# Sheet1.net
KiCad netlist of a schematic drawn in Altium Designer
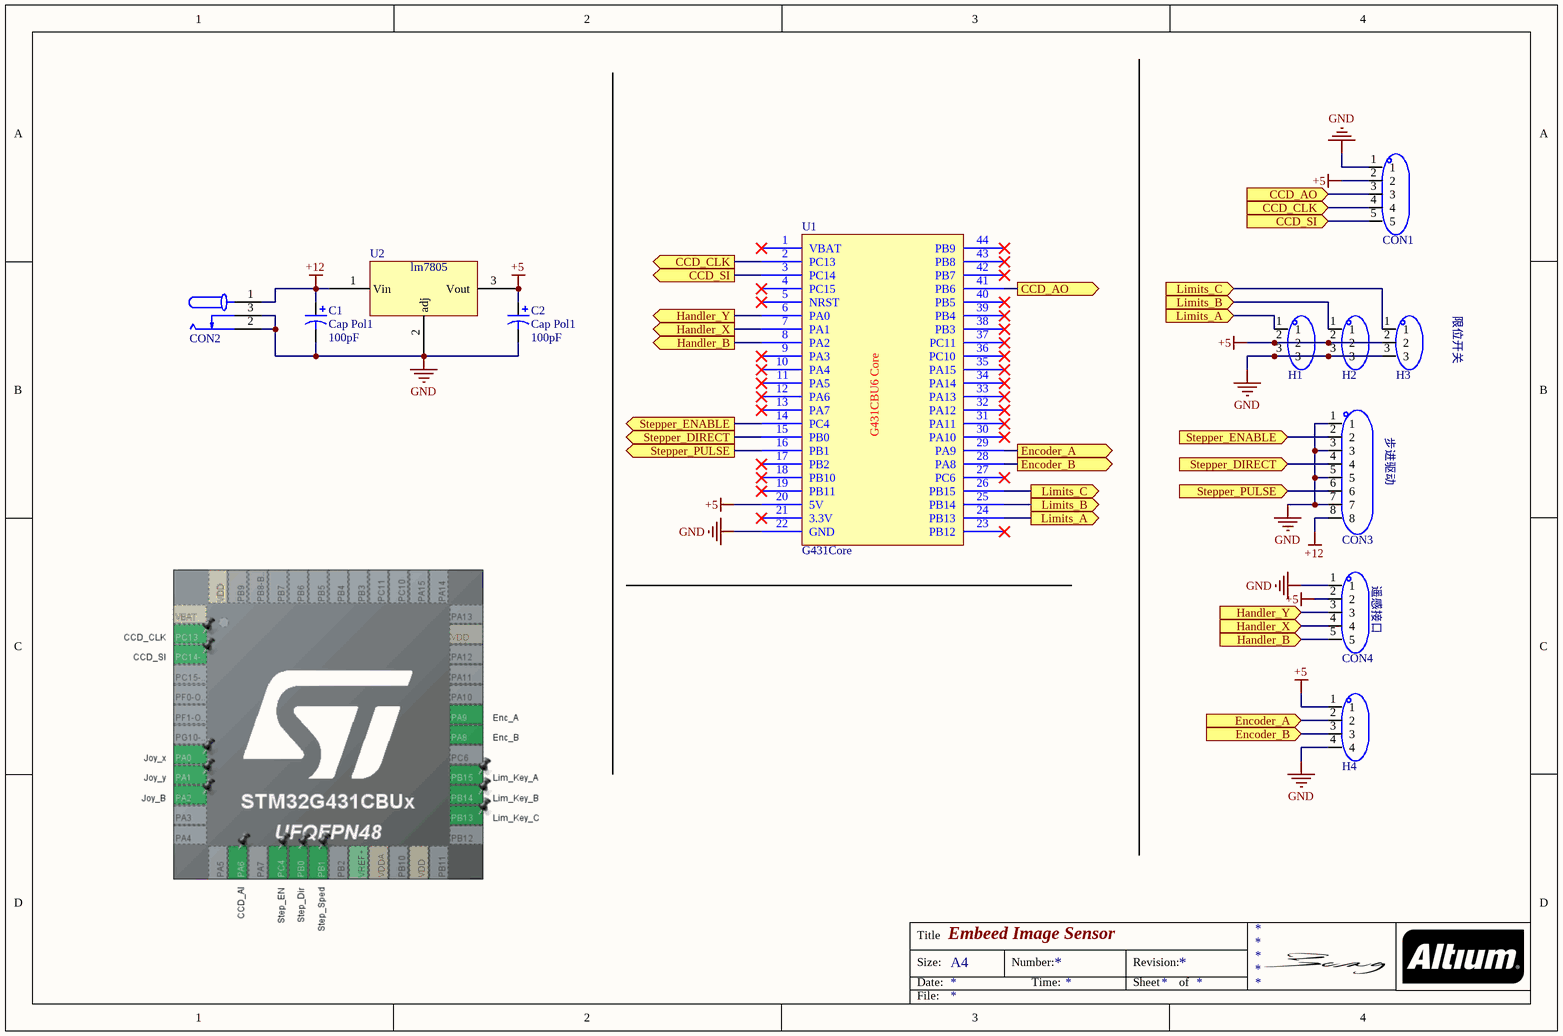
[diagram p0: Sheet1.SchDoc]

(export (version "E")
  (design (tool "Eeschema 10.0.6"))
  (components
    (comp (ref "C1")
      (value "Cap Pol1")
      (footprint "RB7.6-15")
      (description "Polarized Capacitor (Radial)")
      (fields (field (name "ALTIUM_VALUE") "100pF") (field (name "PUBLISHER") "Altium Limited"))
      (libsource (lib "Miscellaneous Devices") (part "Cap Pol1"))
    )
    (comp (ref "C2")
      (value "Cap Pol1")
      (footprint "RB7.6-15")
      (description "Polarized Capacitor (Radial)")
      (fields (field (name "ALTIUM_VALUE") "100pF") (field (name "PUBLISHER") "Altium Limited"))
      (libsource (lib "Miscellaneous Devices") (part "Cap Pol1"))
    )
    (comp (ref "CON1")
      (value "XH2.54-5P")
      (footprint "CONN-TH_5P-P2.50_ZX-XH2.54-5PZZ")
      (fields
        (field (name "MANUFACTURER") "Megastar(兆星)")
        (field (name "MANUFACTURER PART") "ZX-XH2.54-5PZZ")
      )
      (libsource (lib "altium-import") (part "root_0_XH2.54-5P_"))
    )
    (comp (ref "CON2")
      (value "DC_Power_Connector")
      (footprint "DC-IN-TH_DC-005-5A-2.0")
      (fields
        (field (name "MANUFACTURER") "XKB Connection(中国星坤)")
        (field (name "MANUFACTURER PART") "DC-005-5A-2.0")
      )
      (libsource (lib "altium-import") (part "root_0_DC_Power_Connector_"))
    )
    (comp (ref "CON3")
      (value "8Pin_Screw")
      (footprint "CONN-TH_8P-P3.81_WJ15EDGRC-3.81-8P")
      (fields
        (field (name "MANUFACTURER") "KANGNEX(康奈克斯电气)")
        (field (name "MANUFACTURER PART") "WJ15EDGRC-3.81-8P")
      )
      (libsource (lib "altium-import") (part "root_0_8Pin_Screw_"))
    )
    (comp (ref "CON4")
      (value "PH2.0_5Pin")
      (footprint "CONN-TH_5P-P2.00-PH5A")
      (fields (field (name "MANUFACTURER") "XUNPU(讯普)") (field (name "MANUFACTURER PART") "WAFER-PH2.0-5PZZ"))
      (libsource (lib "altium-import") (part "root_0_PH2.0_5Pin_"))
    )
    (comp (ref "H1")
      (value "3Pin_Connector")
      (footprint "HDR-TH_3P-P2.54-V-M")
      (fields (field (name "MANUFACTURER") "XFCN(兴飞)") (field (name "MANUFACTURER PART") "PZ254V-11-03P"))
      (libsource (lib "altium-import") (part "root_0_3Pin_Connector_"))
    )
    (comp (ref "H2")
      (value "3Pin_Connector")
      (footprint "HDR-TH_3P-P2.54-V-M")
      (fields (field (name "MANUFACTURER") "XFCN(兴飞)") (field (name "MANUFACTURER PART") "PZ254V-11-03P"))
      (libsource (lib "altium-import") (part "root_0_3Pin_Connector_"))
    )
    (comp (ref "H3")
      (value "3Pin_Connector")
      (footprint "HDR-TH_3P-P2.54-V-M")
      (fields (field (name "MANUFACTURER") "XFCN(兴飞)") (field (name "MANUFACTURER PART") "PZ254V-11-03P"))
      (libsource (lib "altium-import") (part "root_0_3Pin_Connector_"))
    )
    (comp (ref "H4")
      (value "2.54_4Pin")
      (footprint "HDR-TH_4P-P2.54-V-M")
      (fields (field (name "MANUFACTURER") "XFCN(兴飞)") (field (name "MANUFACTURER PART") "PZ254V-11-04P"))
      (libsource (lib "altium-import") (part "root_0_2.54_4Pin_"))
    )
    (comp (ref "U1")
      (value "G431Core")
      (footprint "PCBComponent_1")
      (libsource (lib "altium-import") (part "root_0_G431Core_"))
    )
    (comp (ref "U2")
      (value "lm7805")
      (footprint "TO-220-3_L10.0-W4.5-P2.54-L")
      (libsource (lib "altium-import") (part "root_0_lm7805_"))
    )
  )
  (nets
    (net (code "1") (name "+5") (class "Default")
      (node (ref "C2") (pin "1") (pinfunction "1_1") (pintype "passive"))
      (node (ref "CON1") (pin "2") (pinfunction "2_2") (pintype "passive"))
      (node (ref "CON4") (pin "2") (pinfunction "2_2") (pintype "passive"))
      (node (ref "H1") (pin "2") (pinfunction "2_2") (pintype "passive"))
      (node (ref "H2") (pin "2") (pinfunction "2_2") (pintype "passive"))
      (node (ref "H3") (pin "2") (pinfunction "2_2") (pintype "passive"))
      (node (ref "H4") (pin "1") (pinfunction "1_1") (pintype "passive"))
      (node (ref "U1") (pin "20") (pinfunction "5V_20") (pintype "passive"))
      (node (ref "U2") (pin "3") (pinfunction "Vout_3") (pintype "passive"))
    )
    (net (code "2") (name "+12") (class "Default")
      (node (ref "C1") (pin "1") (pinfunction "1_1") (pintype "passive"))
      (node (ref "CON2") (pin "1") (pinfunction "1_1") (pintype "passive"))
      (node (ref "CON3") (pin "8") (pinfunction "8_8") (pintype "passive"))
      (node (ref "U2") (pin "1") (pinfunction "Vin_1") (pintype "passive"))
    )
    (net (code "3") (name "/CCD_AO") (class "Default")
      (node (ref "CON1") (pin "3") (pinfunction "3_3") (pintype "passive"))
      (node (ref "U1") (pin "41") (pinfunction "PB6_41") (pintype "passive"))
    )
    (net (code "4") (name "/CCD_CLK") (class "Default")
      (node (ref "CON1") (pin "4") (pinfunction "4_4") (pintype "passive"))
      (node (ref "U1") (pin "2") (pinfunction "PC13_2") (pintype "passive"))
    )
    (net (code "5") (name "/CCD_SI") (class "Default")
      (node (ref "CON1") (pin "5") (pinfunction "5_5") (pintype "passive"))
      (node (ref "U1") (pin "3") (pinfunction "PC14_3") (pintype "passive"))
    )
    (net (code "6") (name "/Encoder_A") (class "Default")
      (node (ref "H4") (pin "2") (pinfunction "2_2") (pintype "passive"))
      (node (ref "U1") (pin "29") (pinfunction "PA9_29") (pintype "passive"))
    )
    (net (code "7") (name "/Encoder_B") (class "Default")
      (node (ref "H4") (pin "3") (pinfunction "3_3") (pintype "passive"))
      (node (ref "U1") (pin "28") (pinfunction "PA8_28") (pintype "passive"))
    )
    (net (code "8") (name "/Handler_B") (class "Default")
      (node (ref "CON4") (pin "5") (pinfunction "5_5") (pintype "passive"))
      (node (ref "U1") (pin "8") (pinfunction "PA2_8") (pintype "passive"))
    )
    (net (code "9") (name "/Handler_X") (class "Default")
      (node (ref "CON4") (pin "4") (pinfunction "4_4") (pintype "passive"))
      (node (ref "U1") (pin "7") (pinfunction "PA1_7") (pintype "passive"))
    )
    (net (code "10") (name "/Handler_Y") (class "Default")
      (node (ref "CON4") (pin "3") (pinfunction "3_3") (pintype "passive"))
      (node (ref "U1") (pin "6") (pinfunction "PA0_6") (pintype "passive"))
    )
    (net (code "11") (name "/Limits_A") (class "Default")
      (node (ref "H1") (pin "1") (pinfunction "1_1") (pintype "passive"))
      (node (ref "U1") (pin "24") (pinfunction "PB13_24") (pintype "passive"))
    )
    (net (code "12") (name "/Limits_B") (class "Default")
      (node (ref "H2") (pin "1") (pinfunction "1_1") (pintype "passive"))
      (node (ref "U1") (pin "25") (pinfunction "PB14_25") (pintype "passive"))
    )
    (net (code "13") (name "/Limits_C") (class "Default")
      (node (ref "H3") (pin "1") (pinfunction "1_1") (pintype "passive"))
      (node (ref "U1") (pin "26") (pinfunction "PB15_26") (pintype "passive"))
    )
    (net (code "14") (name "/Stepper_DIRECT") (class "Default")
      (node (ref "CON3") (pin "4") (pinfunction "4_4") (pintype "passive"))
      (node (ref "U1") (pin "15") (pinfunction "PB0_15") (pintype "passive"))
    )
    (net (code "15") (name "/Stepper_ENABLE") (class "Default")
      (node (ref "CON3") (pin "2") (pinfunction "2_2") (pintype "passive"))
      (node (ref "U1") (pin "14") (pinfunction "PC4_14") (pintype "passive"))
    )
    (net (code "16") (name "/Stepper_PULSE") (class "Default")
      (node (ref "CON3") (pin "6") (pinfunction "6_6") (pintype "passive"))
      (node (ref "U1") (pin "16") (pinfunction "PB1_16") (pintype "passive"))
    )
    (net (code "17") (name "GND") (class "Default")
      (node (ref "C1") (pin "2") (pinfunction "2_2") (pintype "passive"))
      (node (ref "C2") (pin "2") (pinfunction "2_2") (pintype "passive"))
      (node (ref "CON1") (pin "1") (pinfunction "1_1") (pintype "passive"))
      (node (ref "CON2") (pin "2") (pinfunction "2_2") (pintype "passive"))
      (node (ref "CON2") (pin "3") (pinfunction "3_3") (pintype "passive"))
      (node (ref "CON3") (pin "1") (pinfunction "1_1") (pintype "passive"))
      (node (ref "CON3") (pin "3") (pinfunction "3_3") (pintype "passive"))
      (node (ref "CON3") (pin "5") (pinfunction "5_5") (pintype "passive"))
      (node (ref "CON3") (pin "7") (pinfunction "7_7") (pintype "passive"))
      (node (ref "CON4") (pin "1") (pinfunction "1_1") (pintype "passive"))
      (node (ref "H1") (pin "3") (pinfunction "3_3") (pintype "passive"))
      (node (ref "H2") (pin "3") (pinfunction "3_3") (pintype "passive"))
      (node (ref "H3") (pin "3") (pinfunction "3_3") (pintype "passive"))
      (node (ref "H4") (pin "4") (pinfunction "4_4") (pintype "passive"))
      (node (ref "U1") (pin "22") (pinfunction "GND_22") (pintype "passive"))
      (node (ref "U2") (pin "2") (pinfunction "adj_2") (pintype "passive"))
    )
    (net (code "18") (name "unconnected-(U1-3.3V-Pad21)") (class "Default")
      (node (ref "U1") (pin "21") (pinfunction "3.3V_21") (pintype "passive+no_connect"))
    )
    (net (code "19") (name "unconnected-(U1-NRST-Pad5)") (class "Default")
      (node (ref "U1") (pin "5") (pinfunction "NRST_5") (pintype "passive+no_connect"))
    )
    (net (code "20") (name "unconnected-(U1-PA3-Pad9)") (class "Default")
      (node (ref "U1") (pin "9") (pinfunction "PA3_9") (pintype "passive+no_connect"))
    )
    (net (code "21") (name "unconnected-(U1-PA4-Pad10)") (class "Default")
      (node (ref "U1") (pin "10") (pinfunction "PA4_10") (pintype "passive+no_connect"))
    )
    (net (code "22") (name "unconnected-(U1-PA5-Pad11)") (class "Default")
      (node (ref "U1") (pin "11") (pinfunction "PA5_11") (pintype "passive+no_connect"))
    )
    (net (code "23") (name "unconnected-(U1-PA6-Pad12)") (class "Default")
      (node (ref "U1") (pin "12") (pinfunction "PA6_12") (pintype "passive+no_connect"))
    )
    (net (code "24") (name "unconnected-(U1-PA7-Pad13)") (class "Default")
      (node (ref "U1") (pin "13") (pinfunction "PA7_13") (pintype "passive+no_connect"))
    )
    (net (code "25") (name "unconnected-(U1-PA10-Pad30)") (class "Default")
      (node (ref "U1") (pin "30") (pinfunction "PA10_30") (pintype "passive+no_connect"))
    )
    (net (code "26") (name "unconnected-(U1-PA11-Pad31)") (class "Default")
      (node (ref "U1") (pin "31") (pinfunction "PA11_31") (pintype "passive+no_connect"))
    )
    (net (code "27") (name "unconnected-(U1-PA12-Pad32)") (class "Default")
      (node (ref "U1") (pin "32") (pinfunction "PA12_32") (pintype "passive+no_connect"))
    )
    (net (code "28") (name "unconnected-(U1-PA13-Pad33)") (class "Default")
      (node (ref "U1") (pin "33") (pinfunction "PA13_33") (pintype "passive+no_connect"))
    )
    (net (code "29") (name "unconnected-(U1-PA14-Pad34)") (class "Default")
      (node (ref "U1") (pin "34") (pinfunction "PA14_34") (pintype "passive+no_connect"))
    )
    (net (code "30") (name "unconnected-(U1-PA15-Pad35)") (class "Default")
      (node (ref "U1") (pin "35") (pinfunction "PA15_35") (pintype "passive+no_connect"))
    )
    (net (code "31") (name "unconnected-(U1-PB2-Pad17)") (class "Default")
      (node (ref "U1") (pin "17") (pinfunction "PB2_17") (pintype "passive+no_connect"))
    )
    (net (code "32") (name "unconnected-(U1-PB3-Pad38)") (class "Default")
      (node (ref "U1") (pin "38") (pinfunction "PB3_38") (pintype "passive+no_connect"))
    )
    (net (code "33") (name "unconnected-(U1-PB4-Pad39)") (class "Default")
      (node (ref "U1") (pin "39") (pinfunction "PB4_39") (pintype "passive+no_connect"))
    )
    (net (code "34") (name "unconnected-(U1-PB5-Pad40)") (class "Default")
      (node (ref "U1") (pin "40") (pinfunction "PB5_40") (pintype "passive+no_connect"))
    )
    (net (code "35") (name "unconnected-(U1-PB7-Pad42)") (class "Default")
      (node (ref "U1") (pin "42") (pinfunction "PB7_42") (pintype "passive+no_connect"))
    )
    (net (code "36") (name "unconnected-(U1-PB8-Pad43)") (class "Default")
      (node (ref "U1") (pin "43") (pinfunction "PB8_43") (pintype "passive+no_connect"))
    )
    (net (code "37") (name "unconnected-(U1-PB9-Pad44)") (class "Default")
      (node (ref "U1") (pin "44") (pinfunction "PB9_44") (pintype "passive+no_connect"))
    )
    (net (code "38") (name "unconnected-(U1-PB10-Pad18)") (class "Default")
      (node (ref "U1") (pin "18") (pinfunction "PB10_18") (pintype "passive+no_connect"))
    )
    (net (code "39") (name "unconnected-(U1-PB11-Pad19)") (class "Default")
      (node (ref "U1") (pin "19") (pinfunction "PB11_19") (pintype "passive+no_connect"))
    )
    (net (code "40") (name "unconnected-(U1-PB12-Pad23)") (class "Default")
      (node (ref "U1") (pin "23") (pinfunction "PB12_23") (pintype "passive+no_connect"))
    )
    (net (code "41") (name "unconnected-(U1-PC6-Pad27)") (class "Default")
      (node (ref "U1") (pin "27") (pinfunction "PC6_27") (pintype "passive+no_connect"))
    )
    (net (code "42") (name "unconnected-(U1-PC10-Pad36)") (class "Default")
      (node (ref "U1") (pin "36") (pinfunction "PC10_36") (pintype "passive+no_connect"))
    )
    (net (code "43") (name "unconnected-(U1-PC11-Pad37)") (class "Default")
      (node (ref "U1") (pin "37") (pinfunction "PC11_37") (pintype "passive+no_connect"))
    )
    (net (code "44") (name "unconnected-(U1-PC15-Pad4)") (class "Default")
      (node (ref "U1") (pin "4") (pinfunction "PC15_4") (pintype "passive+no_connect"))
    )
    (net (code "45") (name "unconnected-(U1-VBAT-Pad1)") (class "Default")
      (node (ref "U1") (pin "1") (pinfunction "VBAT_1") (pintype "passive+no_connect"))
    )
  )
)
